# UFI_PCB_Rev1.net
KiCad netlist of a schematic drawn in EAGLE
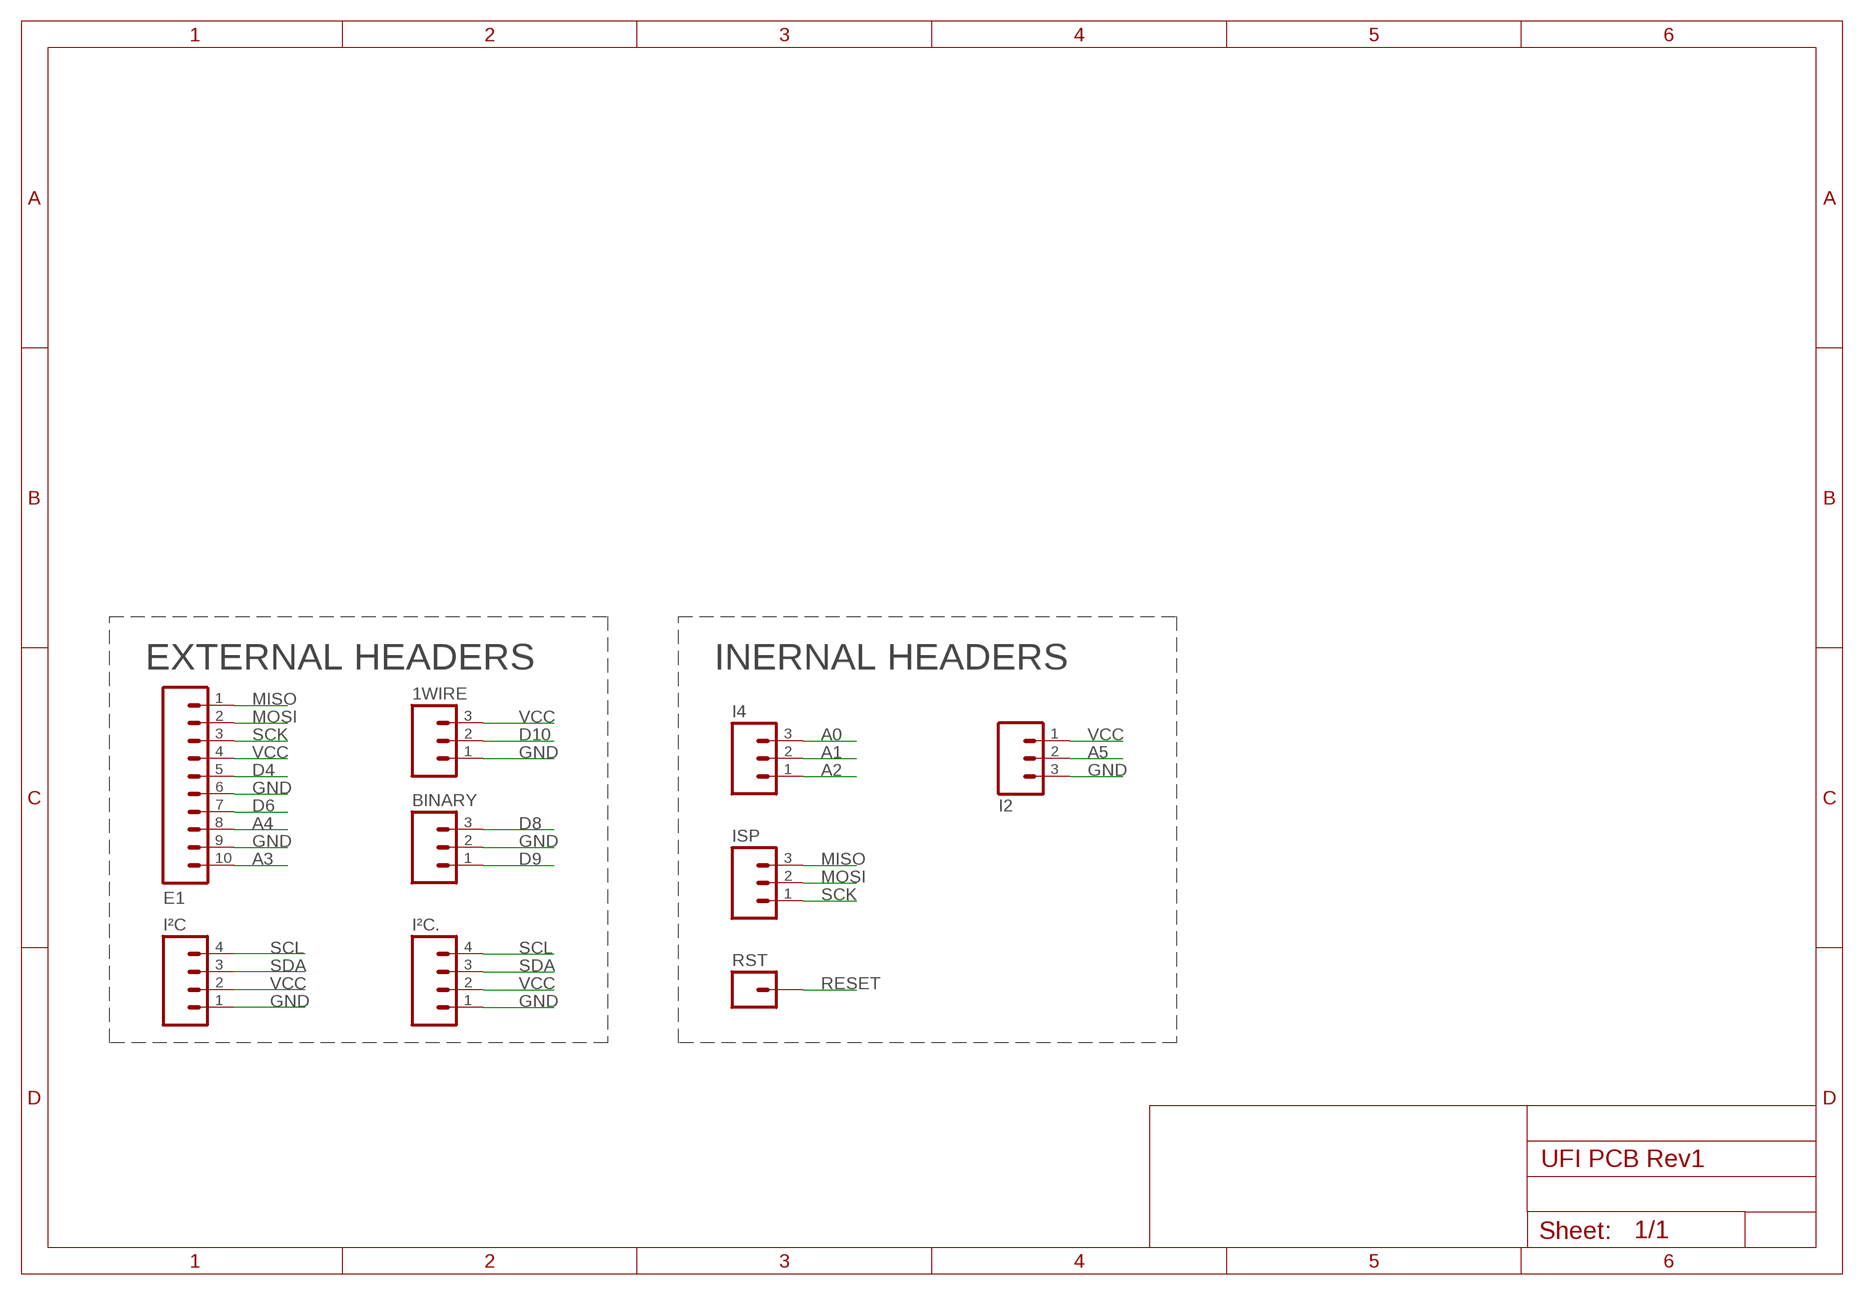
[diagram p0: schematic, sheet 1]

(export (version "E")
  (design (tool "Eeschema 10.0.6"))
  (components
    (comp (ref "1WIRE")
      (value "M031X03_NO_SILK")
      (footprint "eagle-import:1X03_NO_SILK")
      (libsource (lib "eagle-import") (part "M031X03_NO_SILK"))
    )
    (comp (ref "BINARY")
      (value "M031X03_NO_SILK")
      (footprint "eagle-import:1X03_NO_SILK")
      (libsource (lib "eagle-import") (part "M031X03_NO_SILK"))
    )
    (comp (ref "E1")
      (value "M10NO_SILK_PTH_FEMALE")
      (footprint "eagle-import:1X10_NO_SILK")
      (libsource (lib "eagle-import") (part "M10NO_SILK_PTH_FEMALE"))
    )
    (comp (ref "I2")
      (value "M031X03_NO_SILK")
      (footprint "eagle-import:1X03_NO_SILK")
      (libsource (lib "eagle-import") (part "M031X03_NO_SILK"))
    )
    (comp (ref "I4")
      (value "M031X03_NO_SILK")
      (footprint "eagle-import:1X03_NO_SILK")
      (libsource (lib "eagle-import") (part "M031X03_NO_SILK"))
    )
    (comp (ref "ISP")
      (value "M031X03_NO_SILK")
      (footprint "eagle-import:1X03_NO_SILK")
      (libsource (lib "eagle-import") (part "M031X03_NO_SILK"))
    )
    (comp (ref "I²C")
      (value "M04NO_SILK_ALL_ROUND")
      (footprint "eagle-import:1X04_NO_SILK_ALL_ROUND")
      (libsource (lib "eagle-import") (part "M04NO_SILK_ALL_ROUND"))
    )
    (comp (ref "I²C.")
      (value "M04NO_SILK_ALL_ROUND")
      (footprint "eagle-import:1X04_NO_SILK_ALL_ROUND")
      (libsource (lib "eagle-import") (part "M04NO_SILK_ALL_ROUND"))
    )
    (comp (ref "RST")
      (value "M01PTH_NO_SILK_YES_STOP")
      (footprint "eagle-import:1X01_NO_SILK")
      (libsource (lib "eagle-import") (part "M01PTH_NO_SILK_YES_STOP"))
    )
  )
  (nets
    (net (code "1") (name "/A0") (class "Default")
      (node (ref "I4") (pin "3") (pinfunction "3_3") (pintype "passive"))
    )
    (net (code "2") (name "/A1") (class "Default")
      (node (ref "I4") (pin "2") (pinfunction "2_2") (pintype "passive"))
    )
    (net (code "3") (name "/A2") (class "Default")
      (node (ref "I4") (pin "1") (pinfunction "1_1") (pintype "passive"))
    )
    (net (code "4") (name "/A3") (class "Default")
      (node (ref "E1") (pin "10") (pinfunction "10_10") (pintype "passive"))
    )
    (net (code "5") (name "/A4") (class "Default")
      (node (ref "E1") (pin "8") (pinfunction "8_8") (pintype "passive"))
    )
    (net (code "6") (name "/A5") (class "Default")
      (node (ref "I2") (pin "2") (pinfunction "2_2") (pintype "passive"))
    )
    (net (code "7") (name "/D4") (class "Default")
      (node (ref "E1") (pin "5") (pinfunction "5_5") (pintype "passive"))
    )
    (net (code "8") (name "/D6") (class "Default")
      (node (ref "E1") (pin "7") (pinfunction "7_7") (pintype "passive"))
    )
    (net (code "9") (name "/D8") (class "Default")
      (node (ref "BINARY") (pin "3") (pinfunction "3_3") (pintype "passive"))
    )
    (net (code "10") (name "/D9") (class "Default")
      (node (ref "BINARY") (pin "1") (pinfunction "1_1") (pintype "passive"))
    )
    (net (code "11") (name "/D10") (class "Default")
      (node (ref "1WIRE") (pin "2") (pinfunction "2_2") (pintype "passive"))
    )
    (net (code "12") (name "/GND") (class "Default")
      (node (ref "1WIRE") (pin "1") (pinfunction "1_1") (pintype "passive"))
      (node (ref "BINARY") (pin "2") (pinfunction "2_2") (pintype "passive"))
      (node (ref "E1") (pin "6") (pinfunction "6_6") (pintype "passive"))
      (node (ref "E1") (pin "9") (pinfunction "9_9") (pintype "passive"))
      (node (ref "I2") (pin "3") (pinfunction "3_3") (pintype "passive"))
      (node (ref "I²C") (pin "1") (pinfunction "1_1") (pintype "passive"))
      (node (ref "I²C.") (pin "1") (pinfunction "1_1") (pintype "passive"))
    )
    (net (code "13") (name "/MISO") (class "Default")
      (node (ref "E1") (pin "1") (pinfunction "1_1") (pintype "passive"))
      (node (ref "ISP") (pin "3") (pinfunction "3_3") (pintype "passive"))
    )
    (net (code "14") (name "/MOSI") (class "Default")
      (node (ref "E1") (pin "2") (pinfunction "2_2") (pintype "passive"))
      (node (ref "ISP") (pin "2") (pinfunction "2_2") (pintype "passive"))
    )
    (net (code "15") (name "/RESET") (class "Default")
      (node (ref "RST") (pin "1") (pinfunction "1_1") (pintype "passive"))
    )
    (net (code "16") (name "/SCK") (class "Default")
      (node (ref "E1") (pin "3") (pinfunction "3_3") (pintype "passive"))
      (node (ref "ISP") (pin "1") (pinfunction "1_1") (pintype "passive"))
    )
    (net (code "17") (name "/SCL") (class "Default")
      (node (ref "I²C") (pin "4") (pinfunction "4_4") (pintype "passive"))
      (node (ref "I²C.") (pin "4") (pinfunction "4_4") (pintype "passive"))
    )
    (net (code "18") (name "/SDA") (class "Default")
      (node (ref "I²C") (pin "3") (pinfunction "3_3") (pintype "passive"))
      (node (ref "I²C.") (pin "3") (pinfunction "3_3") (pintype "passive"))
    )
    (net (code "19") (name "/VCC") (class "Default")
      (node (ref "1WIRE") (pin "3") (pinfunction "3_3") (pintype "passive"))
      (node (ref "E1") (pin "4") (pinfunction "4_4") (pintype "passive"))
      (node (ref "I2") (pin "1") (pinfunction "1_1") (pintype "passive"))
      (node (ref "I²C") (pin "2") (pinfunction "2_2") (pintype "passive"))
      (node (ref "I²C.") (pin "2") (pinfunction "2_2") (pintype "passive"))
    )
  )
)
